# Flipdot_control.net
KiCad netlist of a schematic drawn in EAGLE
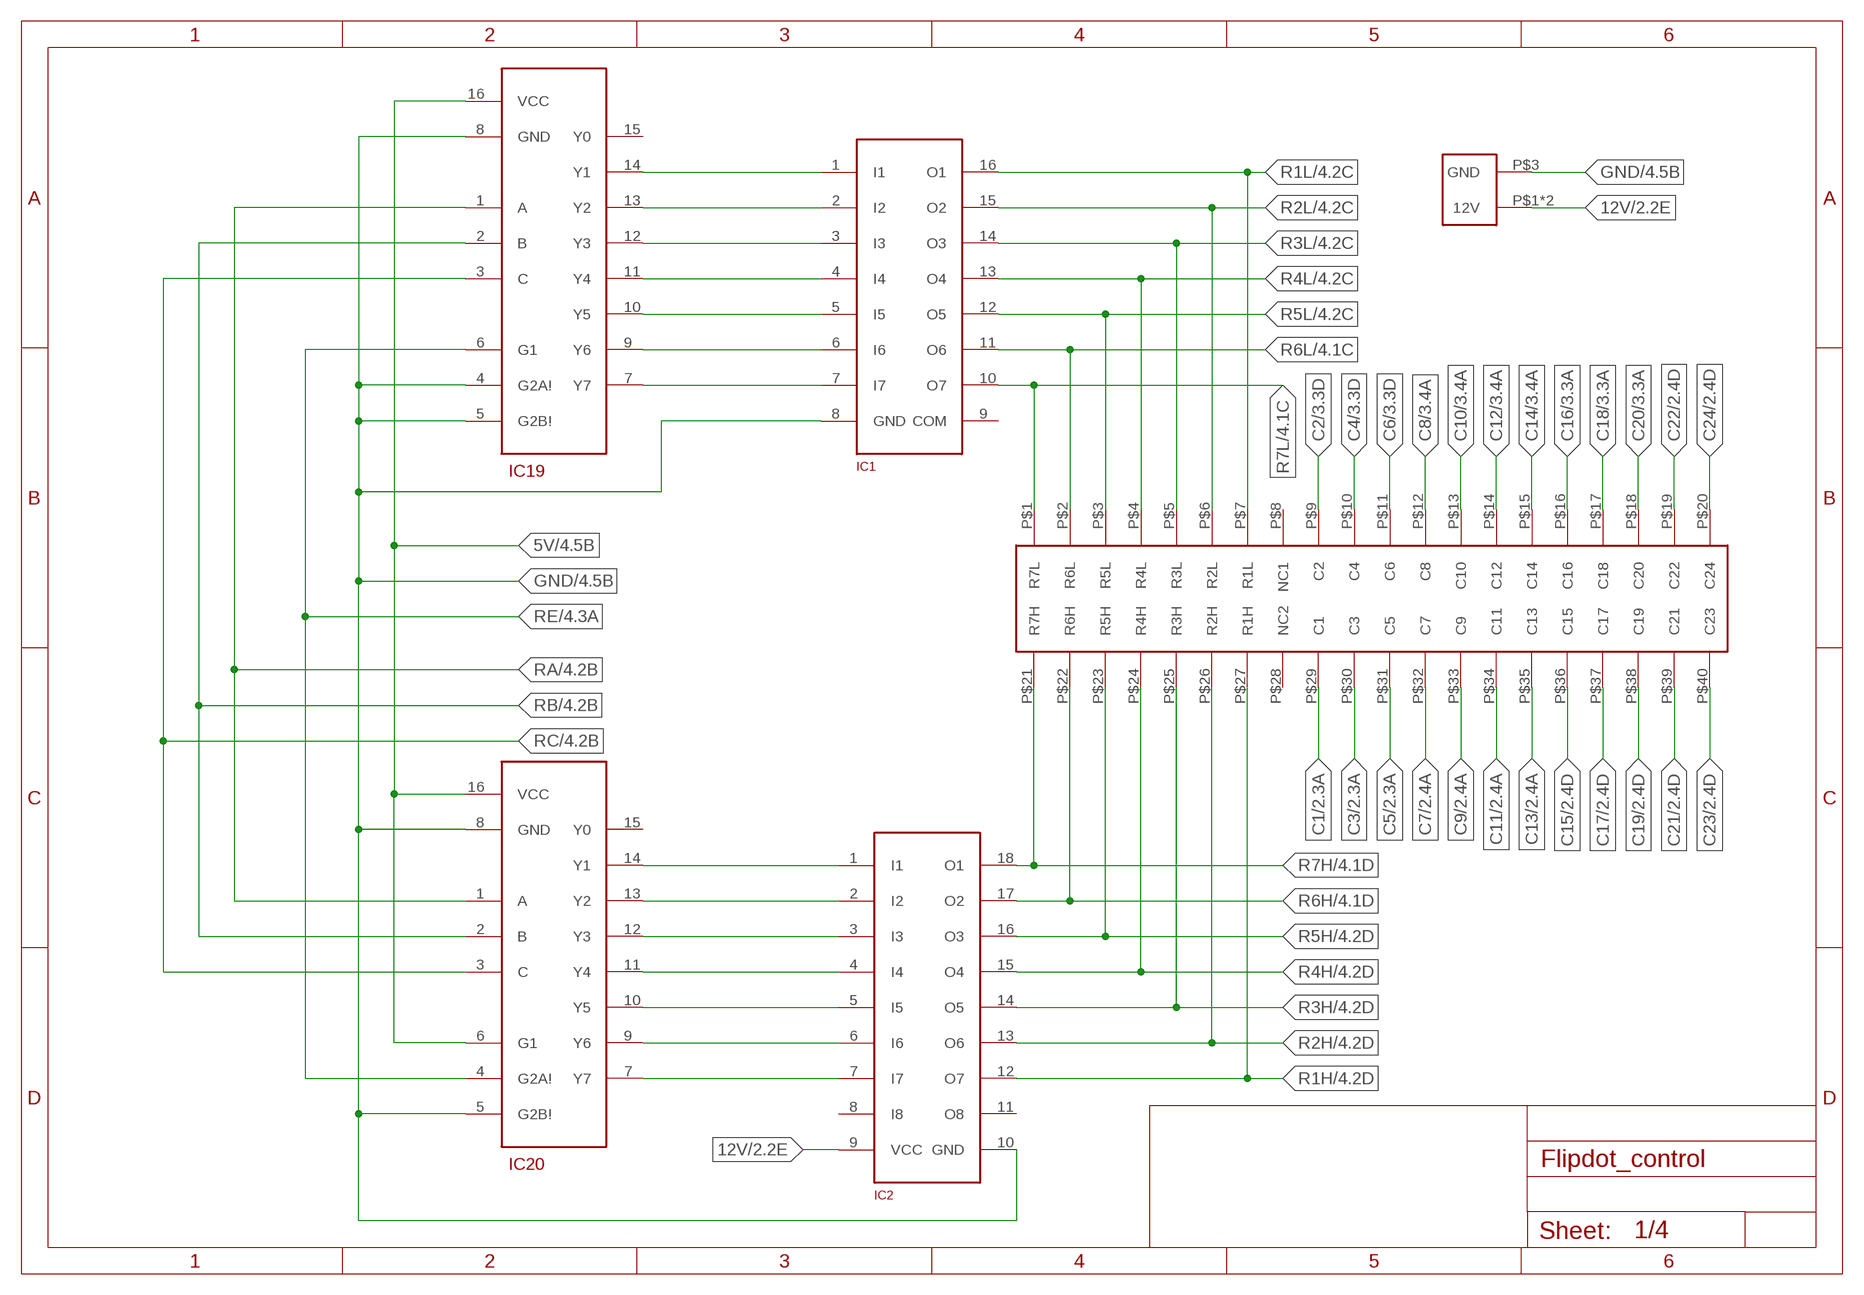
[diagram p0: schematic, sheet 1]
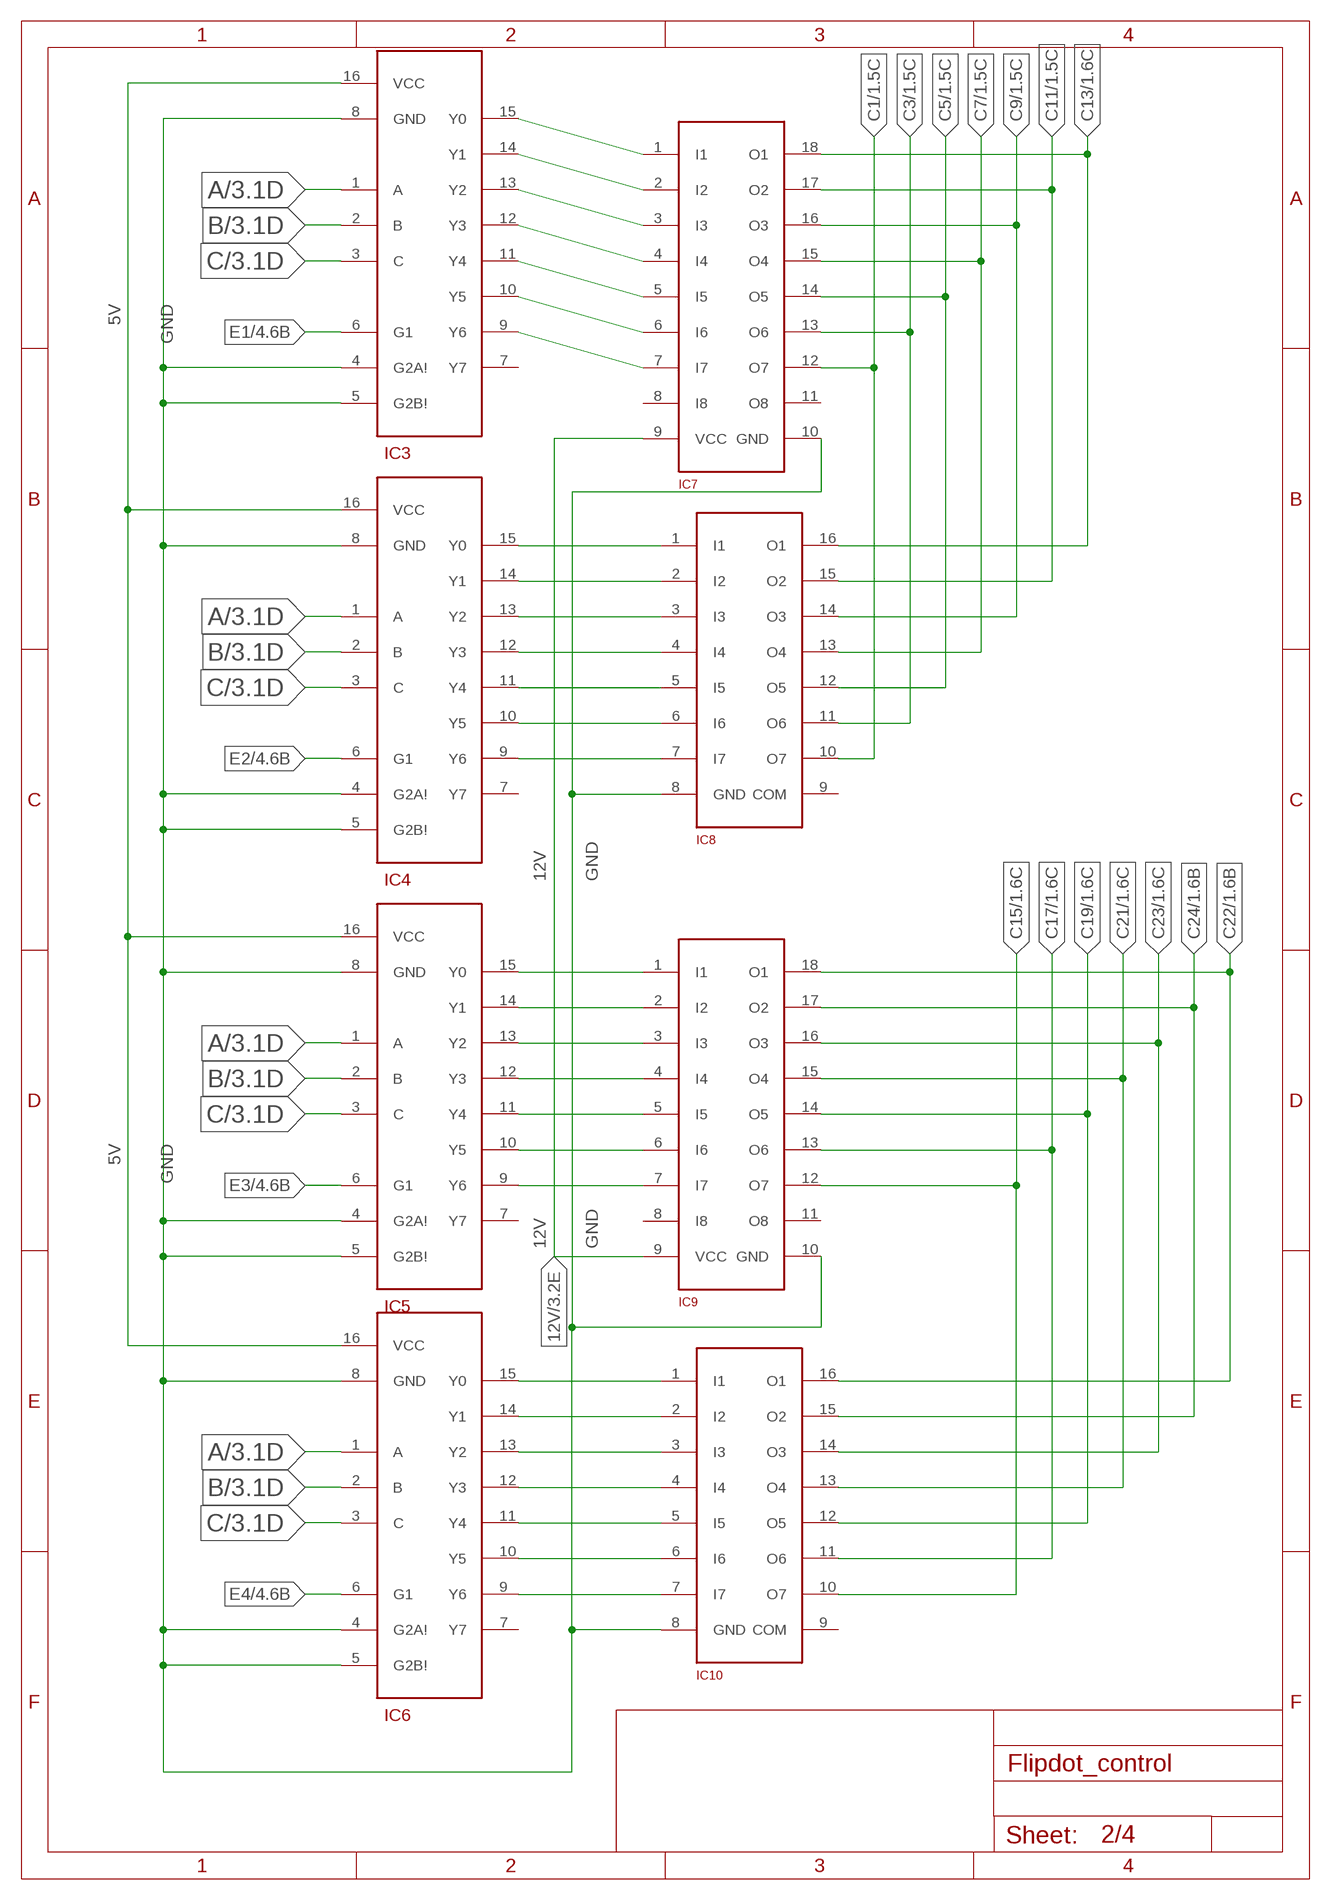
[diagram p1: schematic, sheet 2]
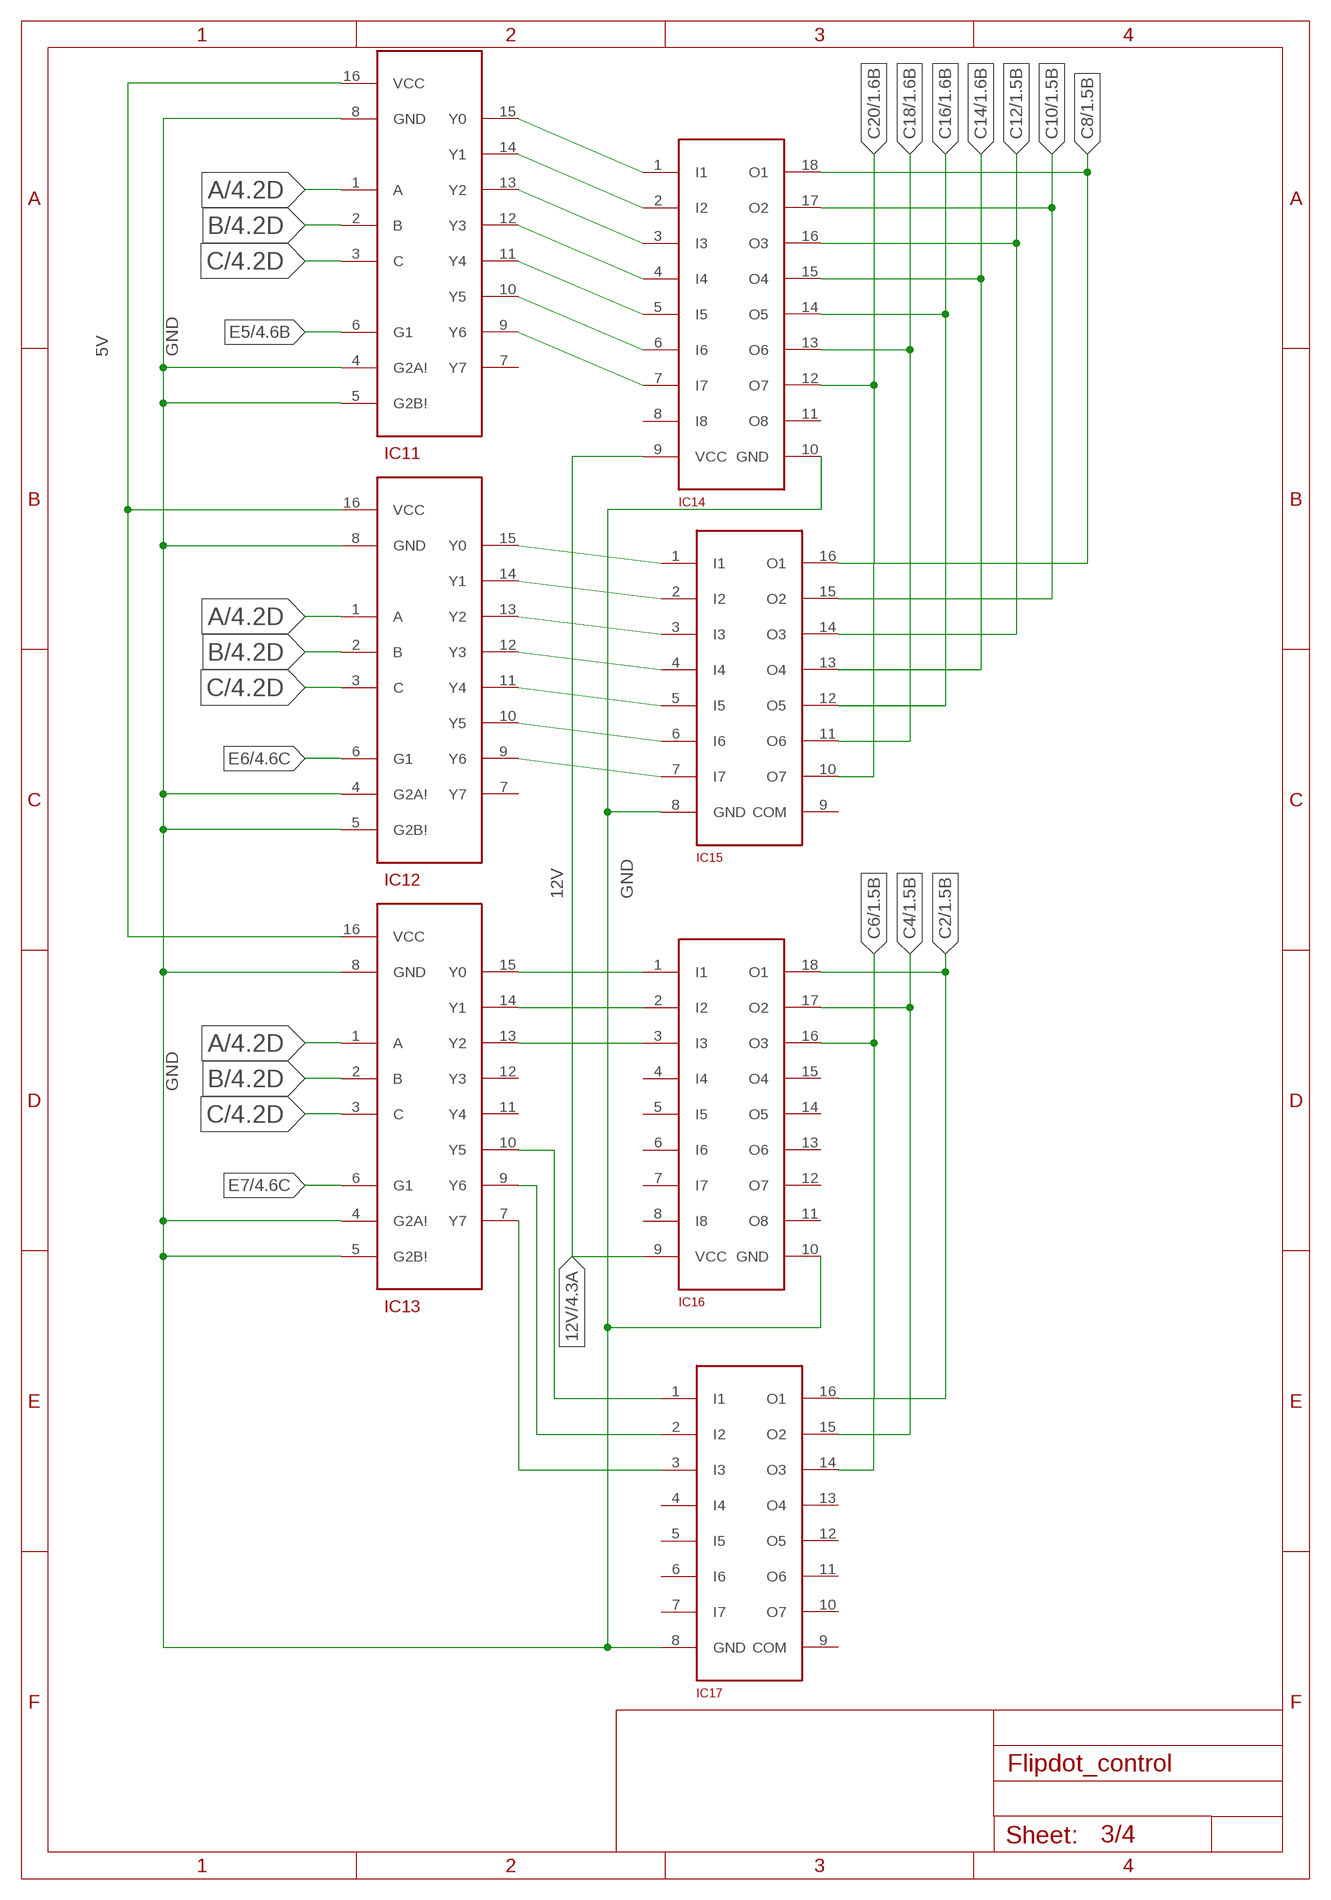
[diagram p2: schematic, sheet 3]
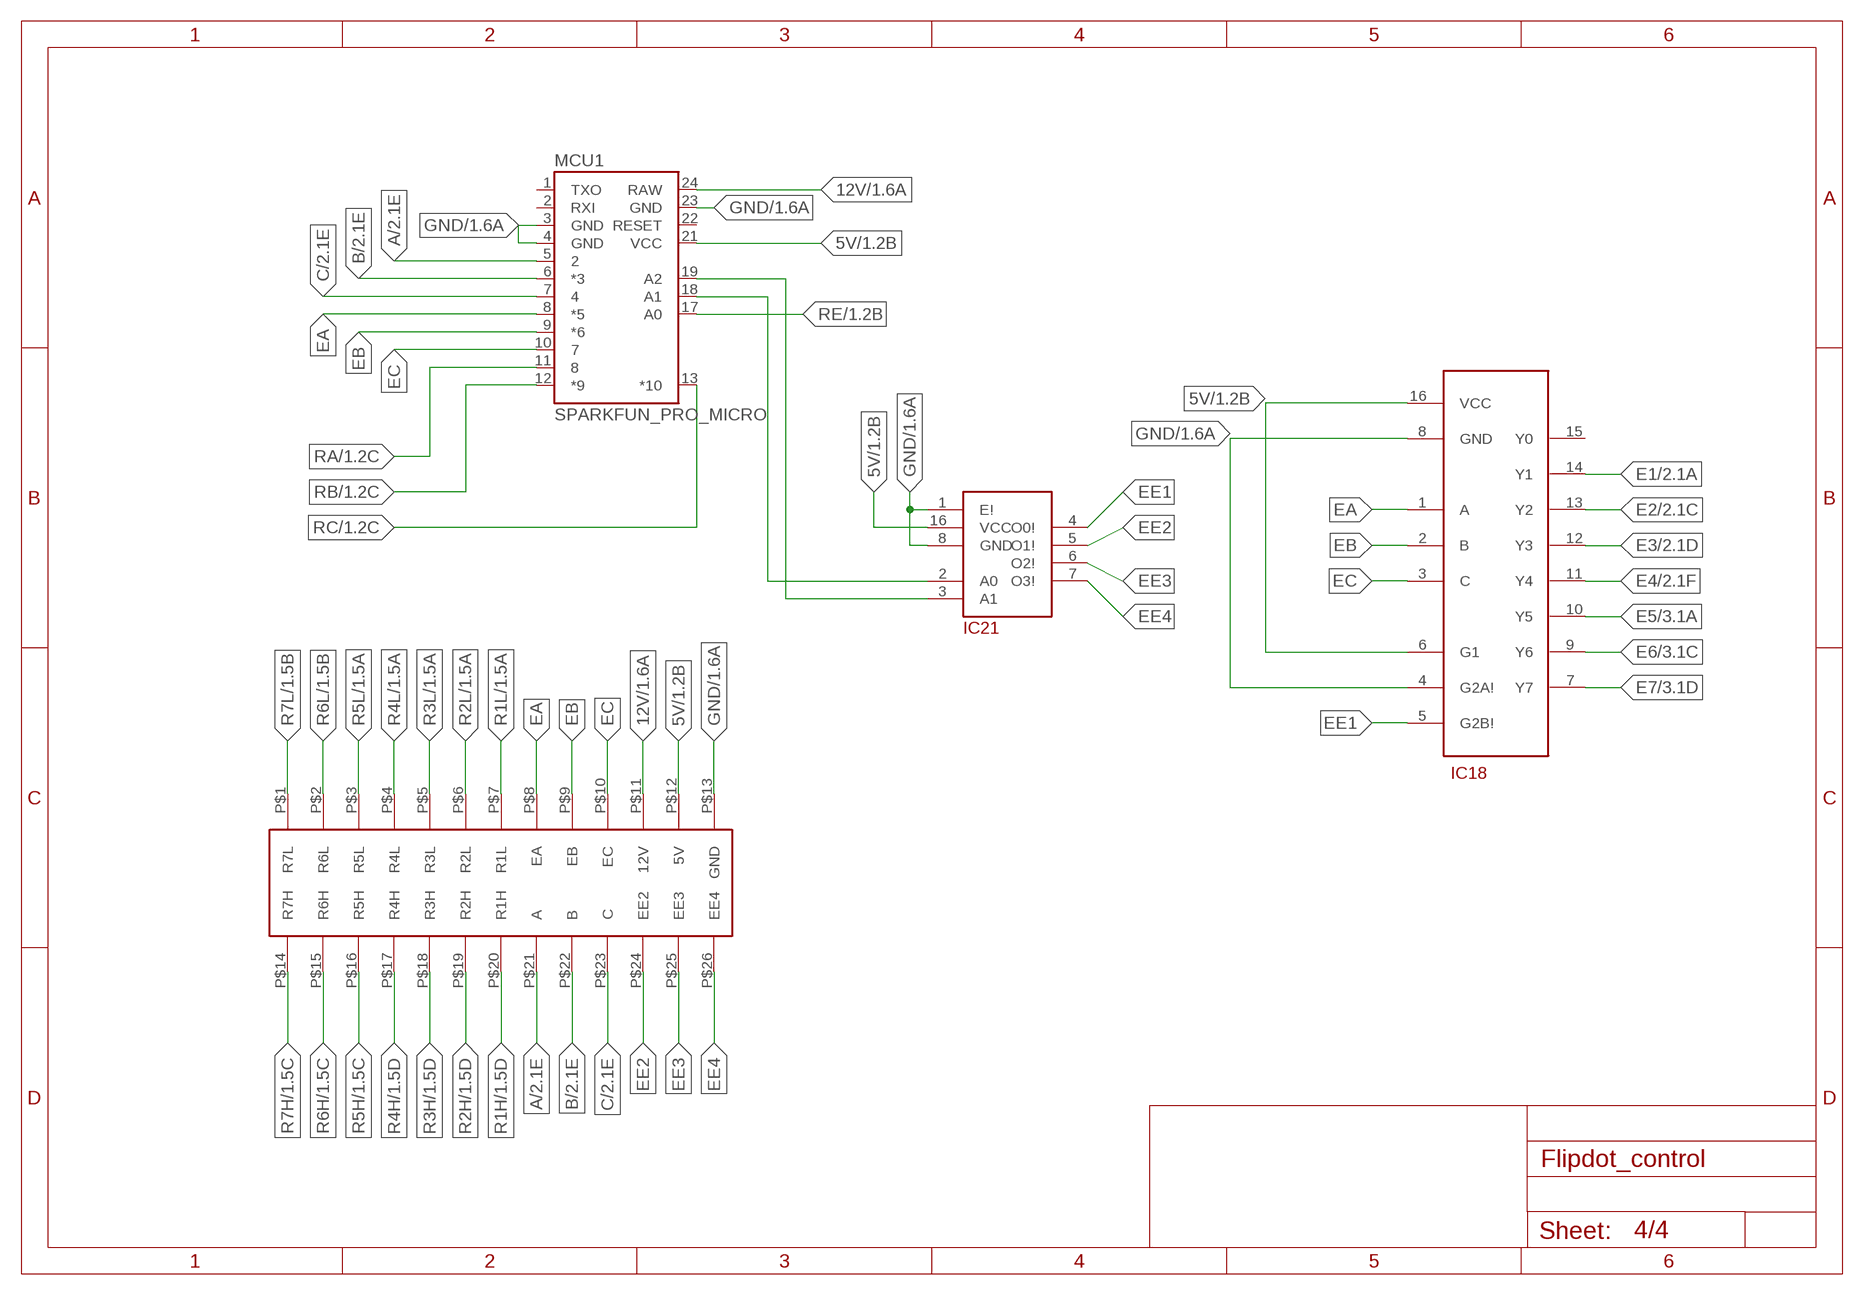
[diagram p3: schematic, sheet 4]

(export (version "E")
  (design (tool "Eeschema 10.0.6"))
  (components
    (comp (ref "IC1")
      (value "ULN2003")
      (footprint "eagle-import:SO16")
      (libsource (lib "eagle-import") (part "ULN2003"))
    )
    (comp (ref "IC2")
      (value "TD62783_AFWG")
      (footprint "eagle-import:SO18W")
      (libsource (lib "eagle-import") (part "TD62783_AFWG"))
    )
    (comp (ref "IC19")
      (value "M74HC238")
      (footprint "eagle-import:SO16")
      (libsource (lib "eagle-import") (part "M74HC238"))
    )
    (comp (ref "IC20")
      (value "M74HC238")
      (footprint "eagle-import:SO16")
      (libsource (lib "eagle-import") (part "M74HC238"))
    )
    (comp (ref "J1")
      (value "HEADER_40")
      (footprint "eagle-import:HEADER_40")
      (libsource (lib "eagle-import") (part "HEADER_40"))
    )
    (comp (ref "U$1") (value "PS") (footprint "eagle-import:PS") (libsource (lib "eagle-import") (part "PS")))
    (comp (ref "IC11")
      (value "M74HC238")
      (footprint "eagle-import:SO16")
      (libsource (lib "eagle-import") (part "M74HC238"))
    )
    (comp (ref "IC12")
      (value "M74HC238")
      (footprint "eagle-import:SO16")
      (libsource (lib "eagle-import") (part "M74HC238"))
    )
    (comp (ref "IC13")
      (value "M74HC238")
      (footprint "eagle-import:SO16")
      (libsource (lib "eagle-import") (part "M74HC238"))
    )
    (comp (ref "IC14")
      (value "TD62783_AFWG")
      (footprint "eagle-import:SO18W")
      (libsource (lib "eagle-import") (part "TD62783_AFWG"))
    )
    (comp (ref "IC15")
      (value "ULN2003")
      (footprint "eagle-import:SO16")
      (libsource (lib "eagle-import") (part "ULN2003"))
    )
    (comp (ref "IC16")
      (value "TD62783_AFWG")
      (footprint "eagle-import:SO18W")
      (libsource (lib "eagle-import") (part "TD62783_AFWG"))
    )
    (comp (ref "IC17")
      (value "ULN2003")
      (footprint "eagle-import:SO16")
      (libsource (lib "eagle-import") (part "ULN2003"))
    )
    (comp (ref "IC18")
      (value "M74HC238")
      (footprint "eagle-import:SO16")
      (libsource (lib "eagle-import") (part "M74HC238"))
    )
    (comp (ref "IC21")
      (value "74AC139SC")
      (footprint "eagle-import:SO16")
      (libsource (lib "eagle-import") (part "74AC139SC"))
    )
    (comp (ref "J2")
      (value "HEADER_26")
      (footprint "eagle-import:HEADER_26")
      (libsource (lib "eagle-import") (part "HEADER_26"))
    )
    (comp (ref "MCU1")
      (value "SPARKFUN_PRO_MICRO")
      (footprint "eagle-import:SPARKFUN_PRO_MICRO")
      (libsource (lib "eagle-import") (part "SPARKFUN_PRO_MICRO"))
    )
    (comp (ref "IC3")
      (value "M74HC238")
      (footprint "eagle-import:SO16")
      (libsource (lib "eagle-import") (part "M74HC238"))
    )
    (comp (ref "IC4")
      (value "M74HC238")
      (footprint "eagle-import:SO16")
      (libsource (lib "eagle-import") (part "M74HC238"))
    )
    (comp (ref "IC5")
      (value "M74HC238")
      (footprint "eagle-import:SO16")
      (libsource (lib "eagle-import") (part "M74HC238"))
    )
    (comp (ref "IC6")
      (value "M74HC238")
      (footprint "eagle-import:SO16")
      (libsource (lib "eagle-import") (part "M74HC238"))
    )
    (comp (ref "IC7")
      (value "TD62783_AFWG")
      (footprint "eagle-import:SO18W")
      (libsource (lib "eagle-import") (part "TD62783_AFWG"))
    )
    (comp (ref "IC8")
      (value "ULN2003")
      (footprint "eagle-import:SO16")
      (libsource (lib "eagle-import") (part "ULN2003"))
    )
    (comp (ref "IC9")
      (value "TD62783_AFWG")
      (footprint "eagle-import:SO18W")
      (libsource (lib "eagle-import") (part "TD62783_AFWG"))
    )
    (comp (ref "IC10")
      (value "ULN2003")
      (footprint "eagle-import:SO16")
      (libsource (lib "eagle-import") (part "ULN2003"))
    )
  )
  (nets
    (net (code "1") (name "5V") (class "Default")
      (node (ref "IC11") (pin "16") (pinfunction "VCC_16") (pintype "bidirectional"))
      (node (ref "IC12") (pin "16") (pinfunction "VCC_16") (pintype "bidirectional"))
      (node (ref "IC13") (pin "16") (pinfunction "VCC_16") (pintype "bidirectional"))
      (node (ref "IC18") (pin "16") (pinfunction "VCC_16") (pintype "bidirectional"))
      (node (ref "IC18") (pin "6") (pinfunction "G1_6") (pintype "bidirectional"))
      (node (ref "IC19") (pin "16") (pinfunction "VCC_16") (pintype "bidirectional"))
      (node (ref "IC20") (pin "16") (pinfunction "VCC_16") (pintype "bidirectional"))
      (node (ref "IC20") (pin "6") (pinfunction "G1_6") (pintype "bidirectional"))
      (node (ref "IC21") (pin "16") (pinfunction "VCC_16") (pintype "bidirectional"))
      (node (ref "IC3") (pin "16") (pinfunction "VCC_16") (pintype "bidirectional"))
      (node (ref "IC4") (pin "16") (pinfunction "VCC_16") (pintype "bidirectional"))
      (node (ref "IC5") (pin "16") (pinfunction "VCC_16") (pintype "bidirectional"))
      (node (ref "IC6") (pin "16") (pinfunction "VCC_16") (pintype "bidirectional"))
      (node (ref "J2") (pin "P$12") (pinfunction "5V_P$12") (pintype "bidirectional"))
      (node (ref "MCU1") (pin "21") (pinfunction "VCC_21") (pintype "power_in"))
    )
    (net (code "2") (name "12V") (class "Default")
      (node (ref "IC14") (pin "9") (pinfunction "VCC_9") (pintype "bidirectional"))
      (node (ref "IC16") (pin "9") (pinfunction "VCC_9") (pintype "bidirectional"))
      (node (ref "IC2") (pin "9") (pinfunction "VCC_9") (pintype "bidirectional"))
      (node (ref "IC7") (pin "9") (pinfunction "VCC_9") (pintype "bidirectional"))
      (node (ref "IC9") (pin "9") (pinfunction "VCC_9") (pintype "bidirectional"))
      (node (ref "J2") (pin "P$11") (pinfunction "12V_P$11") (pintype "bidirectional"))
      (node (ref "MCU1") (pin "24") (pinfunction "RAW_24") (pintype "power_in"))
      (node (ref "U$1") (pin "P$1") (pinfunction "12V_P$1") (pintype "bidirectional"))
      (node (ref "U$1") (pin "P$2") (pinfunction "12V_P$2") (pintype "bidirectional"))
    )
    (net (code "3") (name "A") (class "Default")
      (node (ref "IC11") (pin "1") (pinfunction "A_1") (pintype "bidirectional"))
      (node (ref "IC12") (pin "1") (pinfunction "A_1") (pintype "bidirectional"))
      (node (ref "IC13") (pin "1") (pinfunction "A_1") (pintype "bidirectional"))
      (node (ref "IC3") (pin "1") (pinfunction "A_1") (pintype "bidirectional"))
      (node (ref "IC4") (pin "1") (pinfunction "A_1") (pintype "bidirectional"))
      (node (ref "IC5") (pin "1") (pinfunction "A_1") (pintype "bidirectional"))
      (node (ref "IC6") (pin "1") (pinfunction "A_1") (pintype "bidirectional"))
      (node (ref "J2") (pin "P$21") (pinfunction "A_P$21") (pintype "bidirectional"))
      (node (ref "MCU1") (pin "5") (pinfunction "2_5") (pintype "bidirectional"))
    )
    (net (code "4") (name "B") (class "Default")
      (node (ref "IC11") (pin "2") (pinfunction "B_2") (pintype "bidirectional"))
      (node (ref "IC12") (pin "2") (pinfunction "B_2") (pintype "bidirectional"))
      (node (ref "IC13") (pin "2") (pinfunction "B_2") (pintype "bidirectional"))
      (node (ref "IC3") (pin "2") (pinfunction "B_2") (pintype "bidirectional"))
      (node (ref "IC4") (pin "2") (pinfunction "B_2") (pintype "bidirectional"))
      (node (ref "IC5") (pin "2") (pinfunction "B_2") (pintype "bidirectional"))
      (node (ref "IC6") (pin "2") (pinfunction "B_2") (pintype "bidirectional"))
      (node (ref "J2") (pin "P$22") (pinfunction "B_P$22") (pintype "bidirectional"))
      (node (ref "MCU1") (pin "6") (pinfunction "*3_6") (pintype "bidirectional"))
    )
    (net (code "5") (name "C") (class "Default")
      (node (ref "IC11") (pin "3") (pinfunction "C_3") (pintype "bidirectional"))
      (node (ref "IC12") (pin "3") (pinfunction "C_3") (pintype "bidirectional"))
      (node (ref "IC13") (pin "3") (pinfunction "C_3") (pintype "bidirectional"))
      (node (ref "IC3") (pin "3") (pinfunction "C_3") (pintype "bidirectional"))
      (node (ref "IC4") (pin "3") (pinfunction "C_3") (pintype "bidirectional"))
      (node (ref "IC5") (pin "3") (pinfunction "C_3") (pintype "bidirectional"))
      (node (ref "IC6") (pin "3") (pinfunction "C_3") (pintype "bidirectional"))
      (node (ref "J2") (pin "P$23") (pinfunction "C_P$23") (pintype "bidirectional"))
      (node (ref "MCU1") (pin "7") (pinfunction "4_7") (pintype "bidirectional"))
    )
    (net (code "6") (name "C1") (class "Default")
      (node (ref "IC7") (pin "12") (pinfunction "O7_12") (pintype "bidirectional"))
      (node (ref "IC8") (pin "10") (pinfunction "O7_10") (pintype "bidirectional"))
      (node (ref "J1") (pin "P$29") (pinfunction "C1_P$29") (pintype "bidirectional"))
    )
    (net (code "7") (name "C2") (class "Default")
      (node (ref "IC16") (pin "18") (pinfunction "O1_18") (pintype "bidirectional"))
      (node (ref "IC17") (pin "16") (pinfunction "O1_16") (pintype "bidirectional"))
      (node (ref "J1") (pin "P$9") (pinfunction "C2_P$9") (pintype "bidirectional"))
    )
    (net (code "8") (name "C3") (class "Default")
      (node (ref "IC7") (pin "13") (pinfunction "O6_13") (pintype "bidirectional"))
      (node (ref "IC8") (pin "11") (pinfunction "O6_11") (pintype "bidirectional"))
      (node (ref "J1") (pin "P$30") (pinfunction "C3_P$30") (pintype "bidirectional"))
    )
    (net (code "9") (name "C4") (class "Default")
      (node (ref "IC16") (pin "17") (pinfunction "O2_17") (pintype "bidirectional"))
      (node (ref "IC17") (pin "15") (pinfunction "O2_15") (pintype "bidirectional"))
      (node (ref "J1") (pin "P$10") (pinfunction "C4_P$10") (pintype "bidirectional"))
    )
    (net (code "10") (name "C5") (class "Default")
      (node (ref "IC7") (pin "14") (pinfunction "O5_14") (pintype "bidirectional"))
      (node (ref "IC8") (pin "12") (pinfunction "O5_12") (pintype "bidirectional"))
      (node (ref "J1") (pin "P$31") (pinfunction "C5_P$31") (pintype "bidirectional"))
    )
    (net (code "11") (name "C6") (class "Default")
      (node (ref "IC16") (pin "16") (pinfunction "O3_16") (pintype "bidirectional"))
      (node (ref "IC17") (pin "14") (pinfunction "O3_14") (pintype "bidirectional"))
      (node (ref "J1") (pin "P$11") (pinfunction "C6_P$11") (pintype "bidirectional"))
    )
    (net (code "12") (name "C7") (class "Default")
      (node (ref "IC7") (pin "15") (pinfunction "O4_15") (pintype "bidirectional"))
      (node (ref "IC8") (pin "13") (pinfunction "O4_13") (pintype "bidirectional"))
      (node (ref "J1") (pin "P$32") (pinfunction "C7_P$32") (pintype "bidirectional"))
    )
    (net (code "13") (name "C8") (class "Default")
      (node (ref "IC14") (pin "18") (pinfunction "O1_18") (pintype "bidirectional"))
      (node (ref "IC15") (pin "16") (pinfunction "O1_16") (pintype "bidirectional"))
      (node (ref "J1") (pin "P$12") (pinfunction "C8_P$12") (pintype "bidirectional"))
    )
    (net (code "14") (name "C9") (class "Default")
      (node (ref "IC7") (pin "16") (pinfunction "O3_16") (pintype "bidirectional"))
      (node (ref "IC8") (pin "14") (pinfunction "O3_14") (pintype "bidirectional"))
      (node (ref "J1") (pin "P$33") (pinfunction "C9_P$33") (pintype "bidirectional"))
    )
    (net (code "15") (name "C10") (class "Default")
      (node (ref "IC14") (pin "17") (pinfunction "O2_17") (pintype "bidirectional"))
      (node (ref "IC15") (pin "15") (pinfunction "O2_15") (pintype "bidirectional"))
      (node (ref "J1") (pin "P$13") (pinfunction "C10_P$13") (pintype "bidirectional"))
    )
    (net (code "16") (name "C11") (class "Default")
      (node (ref "IC7") (pin "17") (pinfunction "O2_17") (pintype "bidirectional"))
      (node (ref "IC8") (pin "15") (pinfunction "O2_15") (pintype "bidirectional"))
      (node (ref "J1") (pin "P$34") (pinfunction "C11_P$34") (pintype "bidirectional"))
    )
    (net (code "17") (name "C12") (class "Default")
      (node (ref "IC14") (pin "16") (pinfunction "O3_16") (pintype "bidirectional"))
      (node (ref "IC15") (pin "14") (pinfunction "O3_14") (pintype "bidirectional"))
      (node (ref "J1") (pin "P$14") (pinfunction "C12_P$14") (pintype "bidirectional"))
    )
    (net (code "18") (name "C13") (class "Default")
      (node (ref "IC7") (pin "18") (pinfunction "O1_18") (pintype "bidirectional"))
      (node (ref "IC8") (pin "16") (pinfunction "O1_16") (pintype "bidirectional"))
      (node (ref "J1") (pin "P$35") (pinfunction "C13_P$35") (pintype "bidirectional"))
    )
    (net (code "19") (name "C14") (class "Default")
      (node (ref "IC14") (pin "15") (pinfunction "O4_15") (pintype "bidirectional"))
      (node (ref "IC15") (pin "13") (pinfunction "O4_13") (pintype "bidirectional"))
      (node (ref "J1") (pin "P$15") (pinfunction "C14_P$15") (pintype "bidirectional"))
    )
    (net (code "20") (name "C15") (class "Default")
      (node (ref "IC10") (pin "10") (pinfunction "O7_10") (pintype "bidirectional"))
      (node (ref "IC9") (pin "12") (pinfunction "O7_12") (pintype "bidirectional"))
      (node (ref "J1") (pin "P$36") (pinfunction "C15_P$36") (pintype "bidirectional"))
    )
    (net (code "21") (name "C16") (class "Default")
      (node (ref "IC14") (pin "14") (pinfunction "O5_14") (pintype "bidirectional"))
      (node (ref "IC15") (pin "12") (pinfunction "O5_12") (pintype "bidirectional"))
      (node (ref "J1") (pin "P$16") (pinfunction "C16_P$16") (pintype "bidirectional"))
    )
    (net (code "22") (name "C17") (class "Default")
      (node (ref "IC10") (pin "11") (pinfunction "O6_11") (pintype "bidirectional"))
      (node (ref "IC9") (pin "13") (pinfunction "O6_13") (pintype "bidirectional"))
      (node (ref "J1") (pin "P$37") (pinfunction "C17_P$37") (pintype "bidirectional"))
    )
    (net (code "23") (name "C18") (class "Default")
      (node (ref "IC14") (pin "13") (pinfunction "O6_13") (pintype "bidirectional"))
      (node (ref "IC15") (pin "11") (pinfunction "O6_11") (pintype "bidirectional"))
      (node (ref "J1") (pin "P$17") (pinfunction "C18_P$17") (pintype "bidirectional"))
    )
    (net (code "24") (name "C19") (class "Default")
      (node (ref "IC10") (pin "12") (pinfunction "O5_12") (pintype "bidirectional"))
      (node (ref "IC9") (pin "14") (pinfunction "O5_14") (pintype "bidirectional"))
      (node (ref "J1") (pin "P$38") (pinfunction "C19_P$38") (pintype "bidirectional"))
    )
    (net (code "25") (name "C20") (class "Default")
      (node (ref "IC14") (pin "12") (pinfunction "O7_12") (pintype "bidirectional"))
      (node (ref "IC15") (pin "10") (pinfunction "O7_10") (pintype "bidirectional"))
      (node (ref "J1") (pin "P$18") (pinfunction "C20_P$18") (pintype "bidirectional"))
    )
    (net (code "26") (name "C21") (class "Default")
      (node (ref "IC10") (pin "13") (pinfunction "O4_13") (pintype "bidirectional"))
      (node (ref "IC9") (pin "15") (pinfunction "O4_15") (pintype "bidirectional"))
      (node (ref "J1") (pin "P$39") (pinfunction "C21_P$39") (pintype "bidirectional"))
    )
    (net (code "27") (name "C22") (class "Default")
      (node (ref "IC10") (pin "16") (pinfunction "O1_16") (pintype "bidirectional"))
      (node (ref "IC9") (pin "18") (pinfunction "O1_18") (pintype "bidirectional"))
      (node (ref "J1") (pin "P$19") (pinfunction "C22_P$19") (pintype "bidirectional"))
    )
    (net (code "28") (name "C23") (class "Default")
      (node (ref "IC10") (pin "14") (pinfunction "O3_14") (pintype "bidirectional"))
      (node (ref "IC9") (pin "16") (pinfunction "O3_16") (pintype "bidirectional"))
      (node (ref "J1") (pin "P$40") (pinfunction "C23_P$40") (pintype "bidirectional"))
    )
    (net (code "29") (name "C24") (class "Default")
      (node (ref "IC10") (pin "15") (pinfunction "O2_15") (pintype "bidirectional"))
      (node (ref "IC9") (pin "17") (pinfunction "O2_17") (pintype "bidirectional"))
      (node (ref "J1") (pin "P$20") (pinfunction "C24_P$20") (pintype "bidirectional"))
    )
    (net (code "30") (name "E1") (class "Default")
      (node (ref "IC18") (pin "14") (pinfunction "Y1_14") (pintype "bidirectional"))
      (node (ref "IC3") (pin "6") (pinfunction "G1_6") (pintype "bidirectional"))
    )
    (net (code "31") (name "E2") (class "Default")
      (node (ref "IC18") (pin "13") (pinfunction "Y2_13") (pintype "bidirectional"))
      (node (ref "IC4") (pin "6") (pinfunction "G1_6") (pintype "bidirectional"))
    )
    (net (code "32") (name "E3") (class "Default")
      (node (ref "IC18") (pin "12") (pinfunction "Y3_12") (pintype "bidirectional"))
      (node (ref "IC5") (pin "6") (pinfunction "G1_6") (pintype "bidirectional"))
    )
    (net (code "33") (name "E4") (class "Default")
      (node (ref "IC18") (pin "11") (pinfunction "Y4_11") (pintype "bidirectional"))
      (node (ref "IC6") (pin "6") (pinfunction "G1_6") (pintype "bidirectional"))
    )
    (net (code "34") (name "E5") (class "Default")
      (node (ref "IC11") (pin "6") (pinfunction "G1_6") (pintype "bidirectional"))
      (node (ref "IC18") (pin "10") (pinfunction "Y5_10") (pintype "bidirectional"))
    )
    (net (code "35") (name "E6") (class "Default")
      (node (ref "IC12") (pin "6") (pinfunction "G1_6") (pintype "bidirectional"))
      (node (ref "IC18") (pin "9") (pinfunction "Y6_9") (pintype "bidirectional"))
    )
    (net (code "36") (name "E7") (class "Default")
      (node (ref "IC13") (pin "6") (pinfunction "G1_6") (pintype "bidirectional"))
      (node (ref "IC18") (pin "7") (pinfunction "Y7_7") (pintype "bidirectional"))
    )
    (net (code "37") (name "EA") (class "Default")
      (node (ref "IC18") (pin "1") (pinfunction "A_1") (pintype "bidirectional"))
      (node (ref "J2") (pin "P$8") (pinfunction "EA_P$8") (pintype "bidirectional"))
      (node (ref "MCU1") (pin "8") (pinfunction "*5_8") (pintype "bidirectional"))
    )
    (net (code "38") (name "EB") (class "Default")
      (node (ref "IC18") (pin "2") (pinfunction "B_2") (pintype "bidirectional"))
      (node (ref "J2") (pin "P$9") (pinfunction "EB_P$9") (pintype "bidirectional"))
      (node (ref "MCU1") (pin "9") (pinfunction "*6_9") (pintype "bidirectional"))
    )
    (net (code "39") (name "EC") (class "Default")
      (node (ref "IC18") (pin "3") (pinfunction "C_3") (pintype "bidirectional"))
      (node (ref "J2") (pin "P$10") (pinfunction "EC_P$10") (pintype "bidirectional"))
      (node (ref "MCU1") (pin "10") (pinfunction "7_10") (pintype "bidirectional"))
    )
    (net (code "40") (name "EE1") (class "Default")
      (node (ref "IC18") (pin "5") (pinfunction "G2B~{}_5") (pintype "bidirectional"))
      (node (ref "IC21") (pin "4") (pinfunction "O0~{}_4") (pintype "bidirectional"))
    )
    (net (code "41") (name "EE2") (class "Default")
      (node (ref "IC21") (pin "5") (pinfunction "O1~{}_5") (pintype "bidirectional"))
      (node (ref "J2") (pin "P$24") (pinfunction "EE2_P$24") (pintype "bidirectional"))
    )
    (net (code "42") (name "EE3") (class "Default")
      (node (ref "IC21") (pin "6") (pinfunction "O2~{}_6") (pintype "bidirectional"))
      (node (ref "J2") (pin "P$25") (pinfunction "EE3_P$25") (pintype "bidirectional"))
    )
    (net (code "43") (name "EE4") (class "Default")
      (node (ref "IC21") (pin "7") (pinfunction "O3~{}_7") (pintype "bidirectional"))
      (node (ref "J2") (pin "P$26") (pinfunction "EE4_P$26") (pintype "bidirectional"))
    )
    (net (code "44") (name "GND") (class "Default")
      (node (ref "IC1") (pin "8") (pinfunction "GND_8") (pintype "bidirectional"))
      (node (ref "IC10") (pin "8") (pinfunction "GND_8") (pintype "bidirectional"))
      (node (ref "IC11") (pin "4") (pinfunction "G2A~{}_4") (pintype "bidirectional"))
      (node (ref "IC11") (pin "5") (pinfunction "G2B~{}_5") (pintype "bidirectional"))
      (node (ref "IC11") (pin "8") (pinfunction "GND_8") (pintype "bidirectional"))
      (node (ref "IC12") (pin "4") (pinfunction "G2A~{}_4") (pintype "bidirectional"))
      (node (ref "IC12") (pin "5") (pinfunction "G2B~{}_5") (pintype "bidirectional"))
      (node (ref "IC12") (pin "8") (pinfunction "GND_8") (pintype "bidirectional"))
      (node (ref "IC13") (pin "4") (pinfunction "G2A~{}_4") (pintype "bidirectional"))
      (node (ref "IC13") (pin "5") (pinfunction "G2B~{}_5") (pintype "bidirectional"))
      (node (ref "IC13") (pin "8") (pinfunction "GND_8") (pintype "bidirectional"))
      (node (ref "IC14") (pin "10") (pinfunction "GND_10") (pintype "bidirectional"))
      (node (ref "IC15") (pin "8") (pinfunction "GND_8") (pintype "bidirectional"))
      (node (ref "IC16") (pin "10") (pinfunction "GND_10") (pintype "bidirectional"))
      (node (ref "IC17") (pin "8") (pinfunction "GND_8") (pintype "bidirectional"))
      (node (ref "IC18") (pin "4") (pinfunction "G2A~{}_4") (pintype "bidirectional"))
      (node (ref "IC18") (pin "8") (pinfunction "GND_8") (pintype "bidirectional"))
      (node (ref "IC19") (pin "4") (pinfunction "G2A~{}_4") (pintype "bidirectional"))
      (node (ref "IC19") (pin "5") (pinfunction "G2B~{}_5") (pintype "bidirectional"))
      (node (ref "IC19") (pin "8") (pinfunction "GND_8") (pintype "bidirectional"))
      (node (ref "IC2") (pin "10") (pinfunction "GND_10") (pintype "bidirectional"))
      (node (ref "IC20") (pin "5") (pinfunction "G2B~{}_5") (pintype "bidirectional"))
      (node (ref "IC20") (pin "8") (pinfunction "GND_8") (pintype "bidirectional"))
      (node (ref "IC21") (pin "1") (pinfunction "E~{}_1") (pintype "bidirectional"))
      (node (ref "IC21") (pin "8") (pinfunction "GND_8") (pintype "bidirectional"))
      (node (ref "IC3") (pin "4") (pinfunction "G2A~{}_4") (pintype "bidirectional"))
      (node (ref "IC3") (pin "5") (pinfunction "G2B~{}_5") (pintype "bidirectional"))
      (node (ref "IC3") (pin "8") (pinfunction "GND_8") (pintype "bidirectional"))
      (node (ref "IC4") (pin "4") (pinfunction "G2A~{}_4") (pintype "bidirectional"))
      (node (ref "IC4") (pin "5") (pinfunction "G2B~{}_5") (pintype "bidirectional"))
      (node (ref "IC4") (pin "8") (pinfunction "GND_8") (pintype "bidirectional"))
      (node (ref "IC5") (pin "4") (pinfunction "G2A~{}_4") (pintype "bidirectional"))
      (node (ref "IC5") (pin "5") (pinfunction "G2B~{}_5") (pintype "bidirectional"))
      (node (ref "IC5") (pin "8") (pinfunction "GND_8") (pintype "bidirectional"))
      (node (ref "IC6") (pin "4") (pinfunction "G2A~{}_4") (pintype "bidirectional"))
      (node (ref "IC6") (pin "5") (pinfunction "G2B~{}_5") (pintype "bidirectional"))
      (node (ref "IC6") (pin "8") (pinfunction "GND_8") (pintype "bidirectional"))
      (node (ref "IC7") (pin "10") (pinfunction "GND_10") (pintype "bidirectional"))
      (node (ref "IC8") (pin "8") (pinfunction "GND_8") (pintype "bidirectional"))
      (node (ref "IC9") (pin "10") (pinfunction "GND_10") (pintype "bidirectional"))
      (node (ref "J2") (pin "P$13") (pinfunction "GND_P$13") (pintype "bidirectional"))
      (node (ref "MCU1") (pin "23") (pinfunction "GND_23") (pintype "power_in"))
      (node (ref "MCU1") (pin "3") (pinfunction "GND_3") (pintype "power_in"))
      (node (ref "MCU1") (pin "4") (pinfunction "GND_4") (pintype "power_in"))
      (node (ref "U$1") (pin "P$3") (pinfunction "GND_P$3") (pintype "bidirectional"))
    )
    (net (code "45") (name "Net-(IC1-I1)") (class "Default")
      (node (ref "IC1") (pin "1") (pinfunction "I1_1") (pintype "bidirectional"))
      (node (ref "IC19") (pin "14") (pinfunction "Y1_14") (pintype "bidirectional"))
    )
    (net (code "46") (name "Net-(IC1-I2)") (class "Default")
      (node (ref "IC1") (pin "2") (pinfunction "I2_2") (pintype "bidirectional"))
      (node (ref "IC19") (pin "13") (pinfunction "Y2_13") (pintype "bidirectional"))
    )
    (net (code "47") (name "Net-(IC1-I3)") (class "Default")
      (node (ref "IC1") (pin "3") (pinfunction "I3_3") (pintype "bidirectional"))
      (node (ref "IC19") (pin "12") (pinfunction "Y3_12") (pintype "bidirectional"))
    )
    (net (code "48") (name "Net-(IC1-I4)") (class "Default")
      (node (ref "IC1") (pin "4") (pinfunction "I4_4") (pintype "bidirectional"))
      (node (ref "IC19") (pin "11") (pinfunction "Y4_11") (pintype "bidirectional"))
    )
    (net (code "49") (name "Net-(IC1-I5)") (class "Default")
      (node (ref "IC1") (pin "5") (pinfunction "I5_5") (pintype "bidirectional"))
      (node (ref "IC19") (pin "10") (pinfunction "Y5_10") (pintype "bidirectional"))
    )
    (net (code "50") (name "Net-(IC1-I6)") (class "Default")
      (node (ref "IC1") (pin "6") (pinfunction "I6_6") (pintype "bidirectional"))
      (node (ref "IC19") (pin "9") (pinfunction "Y6_9") (pintype "bidirectional"))
    )
    (net (code "51") (name "Net-(IC1-I7)") (class "Default")
      (node (ref "IC1") (pin "7") (pinfunction "I7_7") (pintype "bidirectional"))
      (node (ref "IC19") (pin "7") (pinfunction "Y7_7") (pintype "bidirectional"))
    )
    (net (code "52") (name "Net-(IC2-I1)") (class "Default")
      (node (ref "IC2") (pin "1") (pinfunction "I1_1") (pintype "bidirectional"))
      (node (ref "IC20") (pin "14") (pinfunction "Y1_14") (pintype "bidirectional"))
    )
    (net (code "53") (name "Net-(IC2-I2)") (class "Default")
      (node (ref "IC2") (pin "2") (pinfunction "I2_2") (pintype "bidirectional"))
      (node (ref "IC20") (pin "13") (pinfunction "Y2_13") (pintype "bidirectional"))
    )
    (net (code "54") (name "Net-(IC2-I3)") (class "Default")
      (node (ref "IC2") (pin "3") (pinfunction "I3_3") (pintype "bidirectional"))
      (node (ref "IC20") (pin "12") (pinfunction "Y3_12") (pintype "bidirectional"))
    )
    (net (code "55") (name "Net-(IC2-I4)") (class "Default")
      (node (ref "IC2") (pin "4") (pinfunction "I4_4") (pintype "bidirectional"))
      (node (ref "IC20") (pin "11") (pinfunction "Y4_11") (pintype "bidirectional"))
    )
    (net (code "56") (name "Net-(IC2-I5)") (class "Default")
      (node (ref "IC2") (pin "5") (pinfunction "I5_5") (pintype "bidirectional"))
      (node (ref "IC20") (pin "10") (pinfunction "Y5_10") (pintype "bidirectional"))
    )
    (net (code "57") (name "Net-(IC2-I6)") (class "Default")
      (node (ref "IC2") (pin "6") (pinfunction "I6_6") (pintype "bidirectional"))
      (node (ref "IC20") (pin "9") (pinfunction "Y6_9") (pintype "bidirectional"))
    )
    (net (code "58") (name "Net-(IC2-I7)") (class "Default")
      (node (ref "IC2") (pin "7") (pinfunction "I7_7") (pintype "bidirectional"))
      (node (ref "IC20") (pin "7") (pinfunction "Y7_7") (pintype "bidirectional"))
    )
    (net (code "59") (name "Net-(IC3-Y0)") (class "Default")
      (node (ref "IC3") (pin "15") (pinfunction "Y0_15") (pintype "bidirectional"))
      (node (ref "IC7") (pin "1") (pinfunction "I1_1") (pintype "bidirectional"))
    )
    (net (code "60") (name "Net-(IC3-Y1)") (class "Default")
      (node (ref "IC3") (pin "14") (pinfunction "Y1_14") (pintype "bidirectional"))
      (node (ref "IC7") (pin "2") (pinfunction "I2_2") (pintype "bidirectional"))
    )
    (net (code "61") (name "Net-(IC3-Y2)") (class "Default")
      (node (ref "IC3") (pin "13") (pinfunction "Y2_13") (pintype "bidirectional"))
      (node (ref "IC7") (pin "3") (pinfunction "I3_3") (pintype "bidirectional"))
    )
    (net (code "62") (name "Net-(IC3-Y3)") (class "Default")
      (node (ref "IC3") (pin "12") (pinfunction "Y3_12") (pintype "bidirectional"))
      (node (ref "IC7") (pin "4") (pinfunction "I4_4") (pintype "bidirectional"))
    )
    (net (code "63") (name "Net-(IC3-Y4)") (class "Default")
      (node (ref "IC3") (pin "11") (pinfunction "Y4_11") (pintype "bidirectional"))
      (node (ref "IC7") (pin "5") (pinfunction "I5_5") (pintype "bidirectional"))
    )
    (net (code "64") (name "Net-(IC3-Y5)") (class "Default")
      (node (ref "IC3") (pin "10") (pinfunction "Y5_10") (pintype "bidirectional"))
      (node (ref "IC7") (pin "6") (pinfunction "I6_6") (pintype "bidirectional"))
    )
    (net (code "65") (name "Net-(IC3-Y6)") (class "Default")
      (node (ref "IC3") (pin "9") (pinfunction "Y6_9") (pintype "bidirectional"))
      (node (ref "IC7") (pin "7") (pinfunction "I7_7") (pintype "bidirectional"))
    )
    (net (code "66") (name "Net-(IC4-Y0)") (class "Default")
      (node (ref "IC4") (pin "15") (pinfunction "Y0_15") (pintype "bidirectional"))
      (node (ref "IC8") (pin "1") (pinfunction "I1_1") (pintype "bidirectional"))
    )
    (net (code "67") (name "Net-(IC4-Y1)") (class "Default")
      (node (ref "IC4") (pin "14") (pinfunction "Y1_14") (pintype "bidirectional"))
      (node (ref "IC8") (pin "2") (pinfunction "I2_2") (pintype "bidirectional"))
    )
    (net (code "68") (name "Net-(IC4-Y2)") (class "Default")
      (node (ref "IC4") (pin "13") (pinfunction "Y2_13") (pintype "bidirectional"))
      (node (ref "IC8") (pin "3") (pinfunction "I3_3") (pintype "bidirectional"))
    )
    (net (code "69") (name "Net-(IC4-Y3)") (class "Default")
      (node (ref "IC4") (pin "12") (pinfunction "Y3_12") (pintype "bidirectional"))
      (node (ref "IC8") (pin "4") (pinfunction "I4_4") (pintype "bidirectional"))
    )
    (net (code "70") (name "Net-(IC4-Y4)") (class "Default")
      (node (ref "IC4") (pin "11") (pinfunction "Y4_11") (pintype "bidirectional"))
      (node (ref "IC8") (pin "5") (pinfunction "I5_5") (pintype "bidirectional"))
    )
    (net (code "71") (name "Net-(IC4-Y5)") (class "Default")
      (node (ref "IC4") (pin "10") (pinfunction "Y5_10") (pintype "bidirectional"))
      (node (ref "IC8") (pin "6") (pinfunction "I6_6") (pintype "bidirectional"))
    )
    (net (code "72") (name "Net-(IC4-Y6)") (class "Default")
      (node (ref "IC4") (pin "9") (pinfunction "Y6_9") (pintype "bidirectional"))
      (node (ref "IC8") (pin "7") (pinfunction "I7_7") (pintype "bidirectional"))
    )
    (net (code "73") (name "Net-(IC5-Y0)") (class "Default")
      (node (ref "IC5") (pin "15") (pinfunction "Y0_15") (pintype "bidirectional"))
      (node (ref "IC9") (pin "1") (pinfunction "I1_1") (pintype "bidirectional"))
    )
    (net (code "74") (name "Net-(IC5-Y1)") (class "Default")
      (node (ref "IC5") (pin "14") (pinfunction "Y1_14") (pintype "bidirectional"))
      (node (ref "IC9") (pin "2") (pinfunction "I2_2") (pintype "bidirectional"))
    )
    (net (code "75") (name "Net-(IC5-Y2)") (class "Default")
      (node (ref "IC5") (pin "13") (pinfunction "Y2_13") (pintype "bidirectional"))
      (node (ref "IC9") (pin "3") (pinfunction "I3_3") (pintype "bidirectional"))
    )
    (net (code "76") (name "Net-(IC5-Y3)") (class "Default")
      (node (ref "IC5") (pin "12") (pinfunction "Y3_12") (pintype "bidirectional"))
      (node (ref "IC9") (pin "4") (pinfunction "I4_4") (pintype "bidirectional"))
    )
    (net (code "77") (name "Net-(IC5-Y4)") (class "Default")
      (node (ref "IC5") (pin "11") (pinfunction "Y4_11") (pintype "bidirectional"))
      (node (ref "IC9") (pin "5") (pinfunction "I5_5") (pintype "bidirectional"))
    )
    (net (code "78") (name "Net-(IC5-Y5)") (class "Default")
      (node (ref "IC5") (pin "10") (pinfunction "Y5_10") (pintype "bidirectional"))
      (node (ref "IC9") (pin "6") (pinfunction "I6_6") (pintype "bidirectional"))
    )
    (net (code "79") (name "Net-(IC5-Y6)") (class "Default")
      (node (ref "IC5") (pin "9") (pinfunction "Y6_9") (pintype "bidirectional"))
      (node (ref "IC9") (pin "7") (pinfunction "I7_7") (pintype "bidirectional"))
    )
    (net (code "80") (name "Net-(IC10-I1)") (class "Default")
      (node (ref "IC10") (pin "1") (pinfunction "I1_1") (pintype "bidirectional"))
      (node (ref "IC6") (pin "15") (pinfunction "Y0_15") (pintype "bidirectional"))
    )
    (net (code "81") (name "Net-(IC10-I2)") (class "Default")
      (node (ref "IC10") (pin "2") (pinfunction "I2_2") (pintype "bidirectional"))
      (node (ref "IC6") (pin "14") (pinfunction "Y1_14") (pintype "bidirectional"))
    )
    (net (code "82") (name "Net-(IC10-I3)") (class "Default")
      (node (ref "IC10") (pin "3") (pinfunction "I3_3") (pintype "bidirectional"))
      (node (ref "IC6") (pin "13") (pinfunction "Y2_13") (pintype "bidirectional"))
    )
    (net (code "83") (name "Net-(IC10-I4)") (class "Default")
      (node (ref "IC10") (pin "4") (pinfunction "I4_4") (pintype "bidirectional"))
      (node (ref "IC6") (pin "12") (pinfunction "Y3_12") (pintype "bidirectional"))
    )
    (net (code "84") (name "Net-(IC10-I5)") (class "Default")
      (node (ref "IC10") (pin "5") (pinfunction "I5_5") (pintype "bidirectional"))
      (node (ref "IC6") (pin "11") (pinfunction "Y4_11") (pintype "bidirectional"))
    )
    (net (code "85") (name "Net-(IC10-I6)") (class "Default")
      (node (ref "IC10") (pin "6") (pinfunction "I6_6") (pintype "bidirectional"))
      (node (ref "IC6") (pin "10") (pinfunction "Y5_10") (pintype "bidirectional"))
    )
    (net (code "86") (name "Net-(IC10-I7)") (class "Default")
      (node (ref "IC10") (pin "7") (pinfunction "I7_7") (pintype "bidirectional"))
      (node (ref "IC6") (pin "9") (pinfunction "Y6_9") (pintype "bidirectional"))
    )
    (net (code "87") (name "Net-(IC11-Y0)") (class "Default")
      (node (ref "IC11") (pin "15") (pinfunction "Y0_15") (pintype "bidirectional"))
      (node (ref "IC14") (pin "1") (pinfunction "I1_1") (pintype "bidirectional"))
    )
    (net (code "88") (name "Net-(IC11-Y1)") (class "Default")
      (node (ref "IC11") (pin "14") (pinfunction "Y1_14") (pintype "bidirectional"))
      (node (ref "IC14") (pin "2") (pinfunction "I2_2") (pintype "bidirectional"))
    )
    (net (code "89") (name "Net-(IC11-Y2)") (class "Default")
      (node (ref "IC11") (pin "13") (pinfunction "Y2_13") (pintype "bidirectional"))
      (node (ref "IC14") (pin "3") (pinfunction "I3_3") (pintype "bidirectional"))
    )
    (net (code "90") (name "Net-(IC11-Y3)") (class "Default")
      (node (ref "IC11") (pin "12") (pinfunction "Y3_12") (pintype "bidirectional"))
      (node (ref "IC14") (pin "4") (pinfunction "I4_4") (pintype "bidirectional"))
    )
    (net (code "91") (name "Net-(IC11-Y4)") (class "Default")
      (node (ref "IC11") (pin "11") (pinfunction "Y4_11") (pintype "bidirectional"))
      (node (ref "IC14") (pin "5") (pinfunction "I5_5") (pintype "bidirectional"))
    )
    (net (code "92") (name "Net-(IC11-Y5)") (class "Default")
      (node (ref "IC11") (pin "10") (pinfunction "Y5_10") (pintype "bidirectional"))
      (node (ref "IC14") (pin "6") (pinfunction "I6_6") (pintype "bidirectional"))
    )
    (net (code "93") (name "Net-(IC11-Y6)") (class "Default")
      (node (ref "IC11") (pin "9") (pinfunction "Y6_9") (pintype "bidirectional"))
      (node (ref "IC14") (pin "7") (pinfunction "I7_7") (pintype "bidirectional"))
    )
    (net (code "94") (name "Net-(IC12-Y0)") (class "Default")
      (node (ref "IC12") (pin "15") (pinfunction "Y0_15") (pintype "bidirectional"))
      (node (ref "IC15") (pin "1") (pinfunction "I1_1") (pintype "bidirectional"))
    )
    (net (code "95") (name "Net-(IC12-Y1)") (class "Default")
      (node (ref "IC12") (pin "14") (pinfunction "Y1_14") (pintype "bidirectional"))
      (node (ref "IC15") (pin "2") (pinfunction "I2_2") (pintype "bidirectional"))
    )
    (net (code "96") (name "Net-(IC12-Y2)") (class "Default")
      (node (ref "IC12") (pin "13") (pinfunction "Y2_13") (pintype "bidirectional"))
      (node (ref "IC15") (pin "3") (pinfunction "I3_3") (pintype "bidirectional"))
    )
    (net (code "97") (name "Net-(IC12-Y3)") (class "Default")
      (node (ref "IC12") (pin "12") (pinfunction "Y3_12") (pintype "bidirectional"))
      (node (ref "IC15") (pin "4") (pinfunction "I4_4") (pintype "bidirectional"))
    )
    (net (code "98") (name "Net-(IC12-Y4)") (class "Default")
      (node (ref "IC12") (pin "11") (pinfunction "Y4_11") (pintype "bidirectional"))
      (node (ref "IC15") (pin "5") (pinfunction "I5_5") (pintype "bidirectional"))
    )
    (net (code "99") (name "Net-(IC12-Y5)") (class "Default")
      (node (ref "IC12") (pin "10") (pinfunction "Y5_10") (pintype "bidirectional"))
      (node (ref "IC15") (pin "6") (pinfunction "I6_6") (pintype "bidirectional"))
    )
    (net (code "100") (name "Net-(IC12-Y6)") (class "Default")
      (node (ref "IC12") (pin "9") (pinfunction "Y6_9") (pintype "bidirectional"))
      (node (ref "IC15") (pin "7") (pinfunction "I7_7") (pintype "bidirectional"))
    )
    (net (code "101") (name "Net-(IC13-Y0)") (class "Default")
      (node (ref "IC13") (pin "15") (pinfunction "Y0_15") (pintype "bidirectional"))
      (node (ref "IC16") (pin "1") (pinfunction "I1_1") (pintype "bidirectional"))
    )
    (net (code "102") (name "Net-(IC13-Y1)") (class "Default")
      (node (ref "IC13") (pin "14") (pinfunction "Y1_14") (pintype "bidirectional"))
      (node (ref "IC16") (pin "2") (pinfunction "I2_2") (pintype "bidirectional"))
    )
    (net (code "103") (name "Net-(IC13-Y2)") (class "Default")
      (node (ref "IC13") (pin "13") (pinfunction "Y2_13") (pintype "bidirectional"))
      (node (ref "IC16") (pin "3") (pinfunction "I3_3") (pintype "bidirectional"))
    )
    (net (code "104") (name "Net-(IC13-Y5)") (class "Default")
      (node (ref "IC13") (pin "10") (pinfunction "Y5_10") (pintype "bidirectional"))
      (node (ref "IC17") (pin "1") (pinfunction "I1_1") (pintype "bidirectional"))
    )
    (net (code "105") (name "Net-(IC13-Y6)") (class "Default")
      (node (ref "IC13") (pin "9") (pinfunction "Y6_9") (pintype "bidirectional"))
      (node (ref "IC17") (pin "2") (pinfunction "I2_2") (pintype "bidirectional"))
    )
    (net (code "106") (name "Net-(IC13-Y7)") (class "Default")
      (node (ref "IC13") (pin "7") (pinfunction "Y7_7") (pintype "bidirectional"))
      (node (ref "IC17") (pin "3") (pinfunction "I3_3") (pintype "bidirectional"))
    )
    (net (code "107") (name "Net-(IC21-A0)") (class "Default")
      (node (ref "IC21") (pin "2") (pinfunction "A0_2") (pintype "bidirectional"))
      (node (ref "MCU1") (pin "18") (pinfunction "A1_18") (pintype "bidirectional"))
    )
    (net (code "108") (name "Net-(IC21-A1)") (class "Default")
      (node (ref "IC21") (pin "3") (pinfunction "A1_3") (pintype "bidirectional"))
      (node (ref "MCU1") (pin "19") (pinfunction "A2_19") (pintype "bidirectional"))
    )
    (net (code "109") (name "R1H") (class "Default")
      (node (ref "IC2") (pin "12") (pinfunction "O7_12") (pintype "bidirectional"))
      (node (ref "J1") (pin "P$27") (pinfunction "R1H_P$27") (pintype "bidirectional"))
      (node (ref "J2") (pin "P$20") (pinfunction "R1H_P$20") (pintype "bidirectional"))
    )
    (net (code "110") (name "R1L") (class "Default")
      (node (ref "IC1") (pin "16") (pinfunction "O1_16") (pintype "bidirectional"))
      (node (ref "J1") (pin "P$7") (pinfunction "R1L_P$7") (pintype "bidirectional"))
      (node (ref "J2") (pin "P$7") (pinfunction "R1L_P$7") (pintype "bidirectional"))
    )
    (net (code "111") (name "R2H") (class "Default")
      (node (ref "IC2") (pin "13") (pinfunction "O6_13") (pintype "bidirectional"))
      (node (ref "J1") (pin "P$26") (pinfunction "R2H_P$26") (pintype "bidirectional"))
      (node (ref "J2") (pin "P$19") (pinfunction "R2H_P$19") (pintype "bidirectional"))
    )
    (net (code "112") (name "R2L") (class "Default")
      (node (ref "IC1") (pin "15") (pinfunction "O2_15") (pintype "bidirectional"))
      (node (ref "J1") (pin "P$6") (pinfunction "R2L_P$6") (pintype "bidirectional"))
      (node (ref "J2") (pin "P$6") (pinfunction "R2L_P$6") (pintype "bidirectional"))
    )
    (net (code "113") (name "R3H") (class "Default")
      (node (ref "IC2") (pin "14") (pinfunction "O5_14") (pintype "bidirectional"))
      (node (ref "J1") (pin "P$25") (pinfunction "R3H_P$25") (pintype "bidirectional"))
      (node (ref "J2") (pin "P$18") (pinfunction "R3H_P$18") (pintype "bidirectional"))
    )
    (net (code "114") (name "R3L") (class "Default")
      (node (ref "IC1") (pin "14") (pinfunction "O3_14") (pintype "bidirectional"))
      (node (ref "J1") (pin "P$5") (pinfunction "R3L_P$5") (pintype "bidirectional"))
      (node (ref "J2") (pin "P$5") (pinfunction "R3L_P$5") (pintype "bidirectional"))
    )
    (net (code "115") (name "R4H") (class "Default")
      (node (ref "IC2") (pin "15") (pinfunction "O4_15") (pintype "bidirectional"))
      (node (ref "J1") (pin "P$24") (pinfunction "R4H_P$24") (pintype "bidirectional"))
      (node (ref "J2") (pin "P$17") (pinfunction "R4H_P$17") (pintype "bidirectional"))
    )
    (net (code "116") (name "R4L") (class "Default")
      (node (ref "IC1") (pin "13") (pinfunction "O4_13") (pintype "bidirectional"))
      (node (ref "J1") (pin "P$4") (pinfunction "R4L_P$4") (pintype "bidirectional"))
      (node (ref "J2") (pin "P$4") (pinfunction "R4L_P$4") (pintype "bidirectional"))
    )
    (net (code "117") (name "R5H") (class "Default")
      (node (ref "IC2") (pin "16") (pinfunction "O3_16") (pintype "bidirectional"))
      (node (ref "J1") (pin "P$23") (pinfunction "R5H_P$23") (pintype "bidirectional"))
      (node (ref "J2") (pin "P$16") (pinfunction "R5H_P$16") (pintype "bidirectional"))
    )
    (net (code "118") (name "R5L") (class "Default")
      (node (ref "IC1") (pin "12") (pinfunction "O5_12") (pintype "bidirectional"))
      (node (ref "J1") (pin "P$3") (pinfunction "R5L_P$3") (pintype "bidirectional"))
      (node (ref "J2") (pin "P$3") (pinfunction "R5L_P$3") (pintype "bidirectional"))
    )
    (net (code "119") (name "R6H") (class "Default")
      (node (ref "IC2") (pin "17") (pinfunction "O2_17") (pintype "bidirectional"))
      (node (ref "J1") (pin "P$22") (pinfunction "R6H_P$22") (pintype "bidirectional"))
      (node (ref "J2") (pin "P$15") (pinfunction "R6H_P$15") (pintype "bidirectional"))
    )
    (net (code "120") (name "R6L") (class "Default")
      (node (ref "IC1") (pin "11") (pinfunction "O6_11") (pintype "bidirectional"))
      (node (ref "J1") (pin "P$2") (pinfunction "R6L_P$2") (pintype "bidirectional"))
      (node (ref "J2") (pin "P$2") (pinfunction "R6L_P$2") (pintype "bidirectional"))
    )
    (net (code "121") (name "R7H") (class "Default")
      (node (ref "IC2") (pin "18") (pinfunction "O1_18") (pintype "bidirectional"))
      (node (ref "J1") (pin "P$21") (pinfunction "R7H_P$21") (pintype "bidirectional"))
      (node (ref "J2") (pin "P$14") (pinfunction "R7H_P$14") (pintype "bidirectional"))
    )
    (net (code "122") (name "R7L") (class "Default")
      (node (ref "IC1") (pin "10") (pinfunction "O7_10") (pintype "bidirectional"))
      (node (ref "J1") (pin "P$1") (pinfunction "R7L_P$1") (pintype "bidirectional"))
      (node (ref "J2") (pin "P$1") (pinfunction "R7L_P$1") (pintype "bidirectional"))
    )
    (net (code "123") (name "RA") (class "Default")
      (node (ref "IC19") (pin "1") (pinfunction "A_1") (pintype "bidirectional"))
      (node (ref "IC20") (pin "1") (pinfunction "A_1") (pintype "bidirectional"))
      (node (ref "MCU1") (pin "11") (pinfunction "8_11") (pintype "bidirectional"))
    )
    (net (code "124") (name "RB") (class "Default")
      (node (ref "IC19") (pin "2") (pinfunction "B_2") (pintype "bidirectional"))
      (node (ref "IC20") (pin "2") (pinfunction "B_2") (pintype "bidirectional"))
      (node (ref "MCU1") (pin "12") (pinfunction "*9_12") (pintype "bidirectional"))
    )
    (net (code "125") (name "RC") (class "Default")
      (node (ref "IC19") (pin "3") (pinfunction "C_3") (pintype "bidirectional"))
      (node (ref "IC20") (pin "3") (pinfunction "C_3") (pintype "bidirectional"))
      (node (ref "MCU1") (pin "13") (pinfunction "*10_13") (pintype "bidirectional"))
    )
    (net (code "126") (name "RE") (class "Default")
      (node (ref "IC19") (pin "6") (pinfunction "G1_6") (pintype "bidirectional"))
      (node (ref "IC20") (pin "4") (pinfunction "G2A~{}_4") (pintype "bidirectional"))
      (node (ref "MCU1") (pin "17") (pinfunction "A0_17") (pintype "bidirectional"))
    )
    (net (code "127") (name "unconnected-(IC1-COM-Pad9)") (class "Default")
      (node (ref "IC1") (pin "9") (pinfunction "COM_9") (pintype "bidirectional"))
    )
    (net (code "128") (name "unconnected-(IC2-I8-Pad8)") (class "Default")
      (node (ref "IC2") (pin "8") (pinfunction "I8_8") (pintype "bidirectional"))
    )
    (net (code "129") (name "unconnected-(IC2-O8-Pad11)") (class "Default")
      (node (ref "IC2") (pin "11") (pinfunction "O8_11") (pintype "bidirectional"))
    )
    (net (code "130") (name "unconnected-(IC3-Y7-Pad7)") (class "Default")
      (node (ref "IC3") (pin "7") (pinfunction "Y7_7") (pintype "bidirectional"))
    )
    (net (code "131") (name "unconnected-(IC4-Y7-Pad7)") (class "Default")
      (node (ref "IC4") (pin "7") (pinfunction "Y7_7") (pintype "bidirectional"))
    )
    (net (code "132") (name "unconnected-(IC5-Y7-Pad7)") (class "Default")
      (node (ref "IC5") (pin "7") (pinfunction "Y7_7") (pintype "bidirectional"))
    )
    (net (code "133") (name "unconnected-(IC6-Y7-Pad7)") (class "Default")
      (node (ref "IC6") (pin "7") (pinfunction "Y7_7") (pintype "bidirectional"))
    )
    (net (code "134") (name "unconnected-(IC7-I8-Pad8)") (class "Default")
      (node (ref "IC7") (pin "8") (pinfunction "I8_8") (pintype "bidirectional"))
    )
    (net (code "135") (name "unconnected-(IC7-O8-Pad11)") (class "Default")
      (node (ref "IC7") (pin "11") (pinfunction "O8_11") (pintype "bidirectional"))
    )
    (net (code "136") (name "unconnected-(IC8-COM-Pad9)") (class "Default")
      (node (ref "IC8") (pin "9") (pinfunction "COM_9") (pintype "bidirectional"))
    )
    (net (code "137") (name "unconnected-(IC9-I8-Pad8)") (class "Default")
      (node (ref "IC9") (pin "8") (pinfunction "I8_8") (pintype "bidirectional"))
    )
    (net (code "138") (name "unconnected-(IC9-O8-Pad11)") (class "Default")
      (node (ref "IC9") (pin "11") (pinfunction "O8_11") (pintype "bidirectional"))
    )
    (net (code "139") (name "unconnected-(IC10-COM-Pad9)") (class "Default")
      (node (ref "IC10") (pin "9") (pinfunction "COM_9") (pintype "bidirectional"))
    )
    (net (code "140") (name "unconnected-(IC11-Y7-Pad7)") (class "Default")
      (node (ref "IC11") (pin "7") (pinfunction "Y7_7") (pintype "bidirectional"))
    )
    (net (code "141") (name "unconnected-(IC12-Y7-Pad7)") (class "Default")
      (node (ref "IC12") (pin "7") (pinfunction "Y7_7") (pintype "bidirectional"))
    )
    (net (code "142") (name "unconnected-(IC13-Y3-Pad12)") (class "Default")
      (node (ref "IC13") (pin "12") (pinfunction "Y3_12") (pintype "bidirectional"))
    )
    (net (code "143") (name "unconnected-(IC13-Y4-Pad11)") (class "Default")
      (node (ref "IC13") (pin "11") (pinfunction "Y4_11") (pintype "bidirectional"))
    )
    (net (code "144") (name "unconnected-(IC14-I8-Pad8)") (class "Default")
      (node (ref "IC14") (pin "8") (pinfunction "I8_8") (pintype "bidirectional"))
    )
    (net (code "145") (name "unconnected-(IC14-O8-Pad11)") (class "Default")
      (node (ref "IC14") (pin "11") (pinfunction "O8_11") (pintype "bidirectional"))
    )
    (net (code "146") (name "unconnected-(IC15-COM-Pad9)") (class "Default")
      (node (ref "IC15") (pin "9") (pinfunction "COM_9") (pintype "bidirectional"))
    )
    (net (code "147") (name "unconnected-(IC16-I4-Pad4)") (class "Default")
      (node (ref "IC16") (pin "4") (pinfunction "I4_4") (pintype "bidirectional"))
    )
    (net (code "148") (name "unconnected-(IC16-I5-Pad5)") (class "Default")
      (node (ref "IC16") (pin "5") (pinfunction "I5_5") (pintype "bidirectional"))
    )
    (net (code "149") (name "unconnected-(IC16-I6-Pad6)") (class "Default")
      (node (ref "IC16") (pin "6") (pinfunction "I6_6") (pintype "bidirectional"))
    )
    (net (code "150") (name "unconnected-(IC16-I7-Pad7)") (class "Default")
      (node (ref "IC16") (pin "7") (pinfunction "I7_7") (pintype "bidirectional"))
    )
    (net (code "151") (name "unconnected-(IC16-I8-Pad8)") (class "Default")
      (node (ref "IC16") (pin "8") (pinfunction "I8_8") (pintype "bidirectional"))
    )
    (net (code "152") (name "unconnected-(IC16-O4-Pad15)") (class "Default")
      (node (ref "IC16") (pin "15") (pinfunction "O4_15") (pintype "bidirectional"))
    )
    (net (code "153") (name "unconnected-(IC16-O5-Pad14)") (class "Default")
      (node (ref "IC16") (pin "14") (pinfunction "O5_14") (pintype "bidirectional"))
    )
    (net (code "154") (name "unconnected-(IC16-O6-Pad13)") (class "Default")
      (node (ref "IC16") (pin "13") (pinfunction "O6_13") (pintype "bidirectional"))
    )
    (net (code "155") (name "unconnected-(IC16-O7-Pad12)") (class "Default")
      (node (ref "IC16") (pin "12") (pinfunction "O7_12") (pintype "bidirectional"))
    )
    (net (code "156") (name "unconnected-(IC16-O8-Pad11)") (class "Default")
      (node (ref "IC16") (pin "11") (pinfunction "O8_11") (pintype "bidirectional"))
    )
    (net (code "157") (name "unconnected-(IC17-COM-Pad9)") (class "Default")
      (node (ref "IC17") (pin "9") (pinfunction "COM_9") (pintype "bidirectional"))
    )
    (net (code "158") (name "unconnected-(IC17-I4-Pad4)") (class "Default")
      (node (ref "IC17") (pin "4") (pinfunction "I4_4") (pintype "bidirectional"))
    )
    (net (code "159") (name "unconnected-(IC17-I5-Pad5)") (class "Default")
      (node (ref "IC17") (pin "5") (pinfunction "I5_5") (pintype "bidirectional"))
    )
    (net (code "160") (name "unconnected-(IC17-I6-Pad6)") (class "Default")
      (node (ref "IC17") (pin "6") (pinfunction "I6_6") (pintype "bidirectional"))
    )
    (net (code "161") (name "unconnected-(IC17-I7-Pad7)") (class "Default")
      (node (ref "IC17") (pin "7") (pinfunction "I7_7") (pintype "bidirectional"))
    )
    (net (code "162") (name "unconnected-(IC17-O4-Pad13)") (class "Default")
      (node (ref "IC17") (pin "13") (pinfunction "O4_13") (pintype "bidirectional"))
    )
    (net (code "163") (name "unconnected-(IC17-O5-Pad12)") (class "Default")
      (node (ref "IC17") (pin "12") (pinfunction "O5_12") (pintype "bidirectional"))
    )
    (net (code "164") (name "unconnected-(IC17-O6-Pad11)") (class "Default")
      (node (ref "IC17") (pin "11") (pinfunction "O6_11") (pintype "bidirectional"))
    )
    (net (code "165") (name "unconnected-(IC17-O7-Pad10)") (class "Default")
      (node (ref "IC17") (pin "10") (pinfunction "O7_10") (pintype "bidirectional"))
    )
    (net (code "166") (name "unconnected-(IC18-Y0-Pad15)") (class "Default")
      (node (ref "IC18") (pin "15") (pinfunction "Y0_15") (pintype "bidirectional"))
    )
    (net (code "167") (name "unconnected-(IC19-Y0-Pad15)") (class "Default")
      (node (ref "IC19") (pin "15") (pinfunction "Y0_15") (pintype "bidirectional"))
    )
    (net (code "168") (name "unconnected-(IC20-Y0-Pad15)") (class "Default")
      (node (ref "IC20") (pin "15") (pinfunction "Y0_15") (pintype "bidirectional"))
    )
    (net (code "169") (name "unconnected-(J1-NC1-PadP$8)") (class "Default")
      (node (ref "J1") (pin "P$8") (pinfunction "NC1_P$8") (pintype "bidirectional"))
    )
    (net (code "170") (name "unconnected-(J1-NC2-PadP$28)") (class "Default")
      (node (ref "J1") (pin "P$28") (pinfunction "NC2_P$28") (pintype "bidirectional"))
    )
    (net (code "171") (name "unconnected-(MCU1-RESET-Pad22)") (class "Default")
      (node (ref "MCU1") (pin "22") (pinfunction "RESET_22") (pintype "bidirectional"))
    )
    (net (code "172") (name "unconnected-(MCU1-RXI-Pad2)") (class "Default")
      (node (ref "MCU1") (pin "2") (pinfunction "RXI_2") (pintype "bidirectional"))
    )
    (net (code "173") (name "unconnected-(MCU1-TXO-Pad1)") (class "Default")
      (node (ref "MCU1") (pin "1") (pinfunction "TXO_1") (pintype "bidirectional"))
    )
  )
)
